# Sheet1.net
KiCad netlist of a schematic drawn in Altium Designer
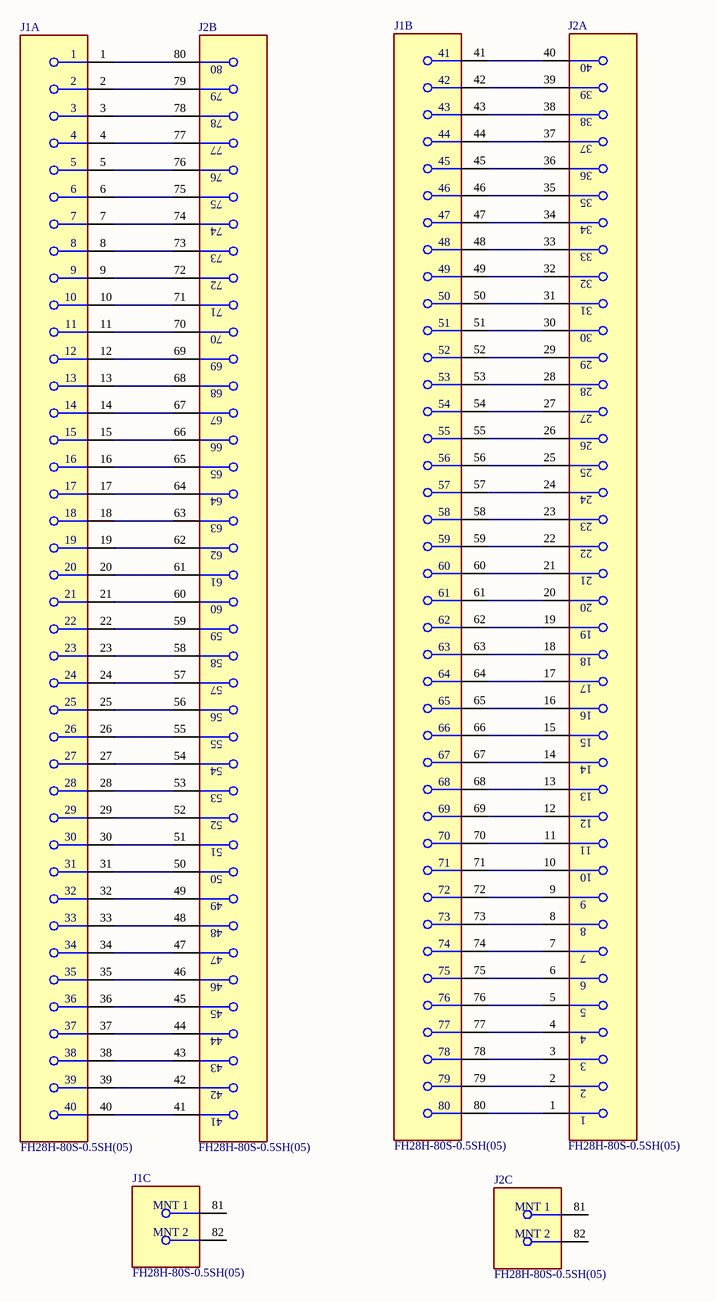
[diagram p0: Sheet1.SchDoc]

(export (version "E")
  (design (tool "Eeschema 10.0.6"))
  (components
    (comp (ref "J1")
      (value "FH28H-80S-0.5SH(05)")
      (footprint "FP-FH28H-80S-0_5SH_05-MFG")
      (description "CONN FFC BOTTOM 80POS 0.50MM R/A")
      (libsource (lib "") (part "08075b3669470a400ec152efcfe4938_1"))
    )
    (comp (ref "J2")
      (value "FH28H-80S-0.5SH(05)")
      (footprint "FP-FH28H-80S-0_5SH_05-MFG")
      (description "CONN FFC BOTTOM 80POS 0.50MM R/A")
      (libsource (lib "") (part "08075b3669470a400ec152efcfe4938_1"))
    )
  )
  (nets
    (net (code "1") (name "Net-(J1-Pad1)") (class "Default")
      (node (ref "J1") (pin "1") (pinfunction "1_1") (pintype "passive"))
      (node (ref "J2") (pin "80") (pinfunction "80_80") (pintype "passive"))
    )
    (net (code "2") (name "Net-(J1-Pad2)") (class "Default")
      (node (ref "J1") (pin "2") (pinfunction "2_2") (pintype "passive"))
      (node (ref "J2") (pin "79") (pinfunction "79_79") (pintype "passive"))
    )
    (net (code "3") (name "Net-(J1-Pad3)") (class "Default")
      (node (ref "J1") (pin "3") (pinfunction "3_3") (pintype "passive"))
      (node (ref "J2") (pin "78") (pinfunction "78_78") (pintype "passive"))
    )
    (net (code "4") (name "Net-(J1-Pad4)") (class "Default")
      (node (ref "J1") (pin "4") (pinfunction "4_4") (pintype "passive"))
      (node (ref "J2") (pin "77") (pinfunction "77_77") (pintype "passive"))
    )
    (net (code "5") (name "Net-(J1-Pad5)") (class "Default")
      (node (ref "J1") (pin "5") (pinfunction "5_5") (pintype "passive"))
      (node (ref "J2") (pin "76") (pinfunction "76_76") (pintype "passive"))
    )
    (net (code "6") (name "Net-(J1-Pad6)") (class "Default")
      (node (ref "J1") (pin "6") (pinfunction "6_6") (pintype "passive"))
      (node (ref "J2") (pin "75") (pinfunction "75_75") (pintype "passive"))
    )
    (net (code "7") (name "Net-(J1-Pad7)") (class "Default")
      (node (ref "J1") (pin "7") (pinfunction "7_7") (pintype "passive"))
      (node (ref "J2") (pin "74") (pinfunction "74_74") (pintype "passive"))
    )
    (net (code "8") (name "Net-(J1-Pad8)") (class "Default")
      (node (ref "J1") (pin "8") (pinfunction "8_8") (pintype "passive"))
      (node (ref "J2") (pin "73") (pinfunction "73_73") (pintype "passive"))
    )
    (net (code "9") (name "Net-(J1-Pad9)") (class "Default")
      (node (ref "J1") (pin "9") (pinfunction "9_9") (pintype "passive"))
      (node (ref "J2") (pin "72") (pinfunction "72_72") (pintype "passive"))
    )
    (net (code "10") (name "Net-(J1-Pad10)") (class "Default")
      (node (ref "J1") (pin "10") (pinfunction "10_10") (pintype "passive"))
      (node (ref "J2") (pin "71") (pinfunction "71_71") (pintype "passive"))
    )
    (net (code "11") (name "Net-(J1-Pad11)") (class "Default")
      (node (ref "J1") (pin "11") (pinfunction "11_11") (pintype "passive"))
      (node (ref "J2") (pin "70") (pinfunction "70_70") (pintype "passive"))
    )
    (net (code "12") (name "Net-(J1-Pad12)") (class "Default")
      (node (ref "J1") (pin "12") (pinfunction "12_12") (pintype "passive"))
      (node (ref "J2") (pin "69") (pinfunction "69_69") (pintype "passive"))
    )
    (net (code "13") (name "Net-(J1-Pad13)") (class "Default")
      (node (ref "J1") (pin "13") (pinfunction "13_13") (pintype "passive"))
      (node (ref "J2") (pin "68") (pinfunction "68_68") (pintype "passive"))
    )
    (net (code "14") (name "Net-(J1-Pad14)") (class "Default")
      (node (ref "J1") (pin "14") (pinfunction "14_14") (pintype "passive"))
      (node (ref "J2") (pin "67") (pinfunction "67_67") (pintype "passive"))
    )
    (net (code "15") (name "Net-(J1-Pad15)") (class "Default")
      (node (ref "J1") (pin "15") (pinfunction "15_15") (pintype "passive"))
      (node (ref "J2") (pin "66") (pinfunction "66_66") (pintype "passive"))
    )
    (net (code "16") (name "Net-(J1-Pad16)") (class "Default")
      (node (ref "J1") (pin "16") (pinfunction "16_16") (pintype "passive"))
      (node (ref "J2") (pin "65") (pinfunction "65_65") (pintype "passive"))
    )
    (net (code "17") (name "Net-(J1-Pad17)") (class "Default")
      (node (ref "J1") (pin "17") (pinfunction "17_17") (pintype "passive"))
      (node (ref "J2") (pin "64") (pinfunction "64_64") (pintype "passive"))
    )
    (net (code "18") (name "Net-(J1-Pad18)") (class "Default")
      (node (ref "J1") (pin "18") (pinfunction "18_18") (pintype "passive"))
      (node (ref "J2") (pin "63") (pinfunction "63_63") (pintype "passive"))
    )
    (net (code "19") (name "Net-(J1-Pad19)") (class "Default")
      (node (ref "J1") (pin "19") (pinfunction "19_19") (pintype "passive"))
      (node (ref "J2") (pin "62") (pinfunction "62_62") (pintype "passive"))
    )
    (net (code "20") (name "Net-(J1-Pad20)") (class "Default")
      (node (ref "J1") (pin "20") (pinfunction "20_20") (pintype "passive"))
      (node (ref "J2") (pin "61") (pinfunction "61_61") (pintype "passive"))
    )
    (net (code "21") (name "Net-(J1-Pad21)") (class "Default")
      (node (ref "J1") (pin "21") (pinfunction "21_21") (pintype "passive"))
      (node (ref "J2") (pin "60") (pinfunction "60_60") (pintype "passive"))
    )
    (net (code "22") (name "Net-(J1-Pad22)") (class "Default")
      (node (ref "J1") (pin "22") (pinfunction "22_22") (pintype "passive"))
      (node (ref "J2") (pin "59") (pinfunction "59_59") (pintype "passive"))
    )
    (net (code "23") (name "Net-(J1-Pad23)") (class "Default")
      (node (ref "J1") (pin "23") (pinfunction "23_23") (pintype "passive"))
      (node (ref "J2") (pin "58") (pinfunction "58_58") (pintype "passive"))
    )
    (net (code "24") (name "Net-(J1-Pad24)") (class "Default")
      (node (ref "J1") (pin "24") (pinfunction "24_24") (pintype "passive"))
      (node (ref "J2") (pin "57") (pinfunction "57_57") (pintype "passive"))
    )
    (net (code "25") (name "Net-(J1-Pad25)") (class "Default")
      (node (ref "J1") (pin "25") (pinfunction "25_25") (pintype "passive"))
      (node (ref "J2") (pin "56") (pinfunction "56_56") (pintype "passive"))
    )
    (net (code "26") (name "Net-(J1-Pad26)") (class "Default")
      (node (ref "J1") (pin "26") (pinfunction "26_26") (pintype "passive"))
      (node (ref "J2") (pin "55") (pinfunction "55_55") (pintype "passive"))
    )
    (net (code "27") (name "Net-(J1-Pad27)") (class "Default")
      (node (ref "J1") (pin "27") (pinfunction "27_27") (pintype "passive"))
      (node (ref "J2") (pin "54") (pinfunction "54_54") (pintype "passive"))
    )
    (net (code "28") (name "Net-(J1-Pad28)") (class "Default")
      (node (ref "J1") (pin "28") (pinfunction "28_28") (pintype "passive"))
      (node (ref "J2") (pin "53") (pinfunction "53_53") (pintype "passive"))
    )
    (net (code "29") (name "Net-(J1-Pad29)") (class "Default")
      (node (ref "J1") (pin "29") (pinfunction "29_29") (pintype "passive"))
      (node (ref "J2") (pin "52") (pinfunction "52_52") (pintype "passive"))
    )
    (net (code "30") (name "Net-(J1-Pad30)") (class "Default")
      (node (ref "J1") (pin "30") (pinfunction "30_30") (pintype "passive"))
      (node (ref "J2") (pin "51") (pinfunction "51_51") (pintype "passive"))
    )
    (net (code "31") (name "Net-(J1-Pad31)") (class "Default")
      (node (ref "J1") (pin "31") (pinfunction "31_31") (pintype "passive"))
      (node (ref "J2") (pin "50") (pinfunction "50_50") (pintype "passive"))
    )
    (net (code "32") (name "Net-(J1-Pad32)") (class "Default")
      (node (ref "J1") (pin "32") (pinfunction "32_32") (pintype "passive"))
      (node (ref "J2") (pin "49") (pinfunction "49_49") (pintype "passive"))
    )
    (net (code "33") (name "Net-(J1-Pad33)") (class "Default")
      (node (ref "J1") (pin "33") (pinfunction "33_33") (pintype "passive"))
      (node (ref "J2") (pin "48") (pinfunction "48_48") (pintype "passive"))
    )
    (net (code "34") (name "Net-(J1-Pad34)") (class "Default")
      (node (ref "J1") (pin "34") (pinfunction "34_34") (pintype "passive"))
      (node (ref "J2") (pin "47") (pinfunction "47_47") (pintype "passive"))
    )
    (net (code "35") (name "Net-(J1-Pad35)") (class "Default")
      (node (ref "J1") (pin "35") (pinfunction "35_35") (pintype "passive"))
      (node (ref "J2") (pin "46") (pinfunction "46_46") (pintype "passive"))
    )
    (net (code "36") (name "Net-(J1-Pad36)") (class "Default")
      (node (ref "J1") (pin "36") (pinfunction "36_36") (pintype "passive"))
      (node (ref "J2") (pin "45") (pinfunction "45_45") (pintype "passive"))
    )
    (net (code "37") (name "Net-(J1-Pad37)") (class "Default")
      (node (ref "J1") (pin "37") (pinfunction "37_37") (pintype "passive"))
      (node (ref "J2") (pin "44") (pinfunction "44_44") (pintype "passive"))
    )
    (net (code "38") (name "Net-(J1-Pad38)") (class "Default")
      (node (ref "J1") (pin "38") (pinfunction "38_38") (pintype "passive"))
      (node (ref "J2") (pin "43") (pinfunction "43_43") (pintype "passive"))
    )
    (net (code "39") (name "Net-(J1-Pad39)") (class "Default")
      (node (ref "J1") (pin "39") (pinfunction "39_39") (pintype "passive"))
      (node (ref "J2") (pin "42") (pinfunction "42_42") (pintype "passive"))
    )
    (net (code "40") (name "Net-(J1-Pad40)") (class "Default")
      (node (ref "J1") (pin "40") (pinfunction "40_40") (pintype "passive"))
      (node (ref "J2") (pin "41") (pinfunction "41_41") (pintype "passive"))
    )
    (net (code "41") (name "Net-(J1-Pad41)") (class "Default")
      (node (ref "J1") (pin "41") (pinfunction "41_41") (pintype "passive"))
      (node (ref "J2") (pin "40") (pinfunction "40_40") (pintype "passive"))
    )
    (net (code "42") (name "Net-(J1-Pad42)") (class "Default")
      (node (ref "J1") (pin "42") (pinfunction "42_42") (pintype "passive"))
      (node (ref "J2") (pin "39") (pinfunction "39_39") (pintype "passive"))
    )
    (net (code "43") (name "Net-(J1-Pad43)") (class "Default")
      (node (ref "J1") (pin "43") (pinfunction "43_43") (pintype "passive"))
      (node (ref "J2") (pin "38") (pinfunction "38_38") (pintype "passive"))
    )
    (net (code "44") (name "Net-(J1-Pad44)") (class "Default")
      (node (ref "J1") (pin "44") (pinfunction "44_44") (pintype "passive"))
      (node (ref "J2") (pin "37") (pinfunction "37_37") (pintype "passive"))
    )
    (net (code "45") (name "Net-(J1-Pad45)") (class "Default")
      (node (ref "J1") (pin "45") (pinfunction "45_45") (pintype "passive"))
      (node (ref "J2") (pin "36") (pinfunction "36_36") (pintype "passive"))
    )
    (net (code "46") (name "Net-(J1-Pad46)") (class "Default")
      (node (ref "J1") (pin "46") (pinfunction "46_46") (pintype "passive"))
      (node (ref "J2") (pin "35") (pinfunction "35_35") (pintype "passive"))
    )
    (net (code "47") (name "Net-(J1-Pad47)") (class "Default")
      (node (ref "J1") (pin "47") (pinfunction "47_47") (pintype "passive"))
      (node (ref "J2") (pin "34") (pinfunction "34_34") (pintype "passive"))
    )
    (net (code "48") (name "Net-(J1-Pad48)") (class "Default")
      (node (ref "J1") (pin "48") (pinfunction "48_48") (pintype "passive"))
      (node (ref "J2") (pin "33") (pinfunction "33_33") (pintype "passive"))
    )
    (net (code "49") (name "Net-(J1-Pad49)") (class "Default")
      (node (ref "J1") (pin "49") (pinfunction "49_49") (pintype "passive"))
      (node (ref "J2") (pin "32") (pinfunction "32_32") (pintype "passive"))
    )
    (net (code "50") (name "Net-(J1-Pad50)") (class "Default")
      (node (ref "J1") (pin "50") (pinfunction "50_50") (pintype "passive"))
      (node (ref "J2") (pin "31") (pinfunction "31_31") (pintype "passive"))
    )
    (net (code "51") (name "Net-(J1-Pad51)") (class "Default")
      (node (ref "J1") (pin "51") (pinfunction "51_51") (pintype "passive"))
      (node (ref "J2") (pin "30") (pinfunction "30_30") (pintype "passive"))
    )
    (net (code "52") (name "Net-(J1-Pad52)") (class "Default")
      (node (ref "J1") (pin "52") (pinfunction "52_52") (pintype "passive"))
      (node (ref "J2") (pin "29") (pinfunction "29_29") (pintype "passive"))
    )
    (net (code "53") (name "Net-(J1-Pad53)") (class "Default")
      (node (ref "J1") (pin "53") (pinfunction "53_53") (pintype "passive"))
      (node (ref "J2") (pin "28") (pinfunction "28_28") (pintype "passive"))
    )
    (net (code "54") (name "Net-(J1-Pad54)") (class "Default")
      (node (ref "J1") (pin "54") (pinfunction "54_54") (pintype "passive"))
      (node (ref "J2") (pin "27") (pinfunction "27_27") (pintype "passive"))
    )
    (net (code "55") (name "Net-(J1-Pad55)") (class "Default")
      (node (ref "J1") (pin "55") (pinfunction "55_55") (pintype "passive"))
      (node (ref "J2") (pin "26") (pinfunction "26_26") (pintype "passive"))
    )
    (net (code "56") (name "Net-(J1-Pad56)") (class "Default")
      (node (ref "J1") (pin "56") (pinfunction "56_56") (pintype "passive"))
      (node (ref "J2") (pin "25") (pinfunction "25_25") (pintype "passive"))
    )
    (net (code "57") (name "Net-(J1-Pad57)") (class "Default")
      (node (ref "J1") (pin "57") (pinfunction "57_57") (pintype "passive"))
      (node (ref "J2") (pin "24") (pinfunction "24_24") (pintype "passive"))
    )
    (net (code "58") (name "Net-(J1-Pad58)") (class "Default")
      (node (ref "J1") (pin "58") (pinfunction "58_58") (pintype "passive"))
      (node (ref "J2") (pin "23") (pinfunction "23_23") (pintype "passive"))
    )
    (net (code "59") (name "Net-(J1-Pad59)") (class "Default")
      (node (ref "J1") (pin "59") (pinfunction "59_59") (pintype "passive"))
      (node (ref "J2") (pin "22") (pinfunction "22_22") (pintype "passive"))
    )
    (net (code "60") (name "Net-(J1-Pad60)") (class "Default")
      (node (ref "J1") (pin "60") (pinfunction "60_60") (pintype "passive"))
      (node (ref "J2") (pin "21") (pinfunction "21_21") (pintype "passive"))
    )
    (net (code "61") (name "Net-(J1-Pad61)") (class "Default")
      (node (ref "J1") (pin "61") (pinfunction "61_61") (pintype "passive"))
      (node (ref "J2") (pin "20") (pinfunction "20_20") (pintype "passive"))
    )
    (net (code "62") (name "Net-(J1-Pad62)") (class "Default")
      (node (ref "J1") (pin "62") (pinfunction "62_62") (pintype "passive"))
      (node (ref "J2") (pin "19") (pinfunction "19_19") (pintype "passive"))
    )
    (net (code "63") (name "Net-(J1-Pad63)") (class "Default")
      (node (ref "J1") (pin "63") (pinfunction "63_63") (pintype "passive"))
      (node (ref "J2") (pin "18") (pinfunction "18_18") (pintype "passive"))
    )
    (net (code "64") (name "Net-(J1-Pad64)") (class "Default")
      (node (ref "J1") (pin "64") (pinfunction "64_64") (pintype "passive"))
      (node (ref "J2") (pin "17") (pinfunction "17_17") (pintype "passive"))
    )
    (net (code "65") (name "Net-(J1-Pad65)") (class "Default")
      (node (ref "J1") (pin "65") (pinfunction "65_65") (pintype "passive"))
      (node (ref "J2") (pin "16") (pinfunction "16_16") (pintype "passive"))
    )
    (net (code "66") (name "Net-(J1-Pad66)") (class "Default")
      (node (ref "J1") (pin "66") (pinfunction "66_66") (pintype "passive"))
      (node (ref "J2") (pin "15") (pinfunction "15_15") (pintype "passive"))
    )
    (net (code "67") (name "Net-(J1-Pad67)") (class "Default")
      (node (ref "J1") (pin "67") (pinfunction "67_67") (pintype "passive"))
      (node (ref "J2") (pin "14") (pinfunction "14_14") (pintype "passive"))
    )
    (net (code "68") (name "Net-(J1-Pad68)") (class "Default")
      (node (ref "J1") (pin "68") (pinfunction "68_68") (pintype "passive"))
      (node (ref "J2") (pin "13") (pinfunction "13_13") (pintype "passive"))
    )
    (net (code "69") (name "Net-(J1-Pad69)") (class "Default")
      (node (ref "J1") (pin "69") (pinfunction "69_69") (pintype "passive"))
      (node (ref "J2") (pin "12") (pinfunction "12_12") (pintype "passive"))
    )
    (net (code "70") (name "Net-(J1-Pad70)") (class "Default")
      (node (ref "J1") (pin "70") (pinfunction "70_70") (pintype "passive"))
      (node (ref "J2") (pin "11") (pinfunction "11_11") (pintype "passive"))
    )
    (net (code "71") (name "Net-(J1-Pad71)") (class "Default")
      (node (ref "J1") (pin "71") (pinfunction "71_71") (pintype "passive"))
      (node (ref "J2") (pin "10") (pinfunction "10_10") (pintype "passive"))
    )
    (net (code "72") (name "Net-(J1-Pad72)") (class "Default")
      (node (ref "J1") (pin "72") (pinfunction "72_72") (pintype "passive"))
      (node (ref "J2") (pin "9") (pinfunction "9_9") (pintype "passive"))
    )
    (net (code "73") (name "Net-(J1-Pad73)") (class "Default")
      (node (ref "J1") (pin "73") (pinfunction "73_73") (pintype "passive"))
      (node (ref "J2") (pin "8") (pinfunction "8_8") (pintype "passive"))
    )
    (net (code "74") (name "Net-(J1-Pad74)") (class "Default")
      (node (ref "J1") (pin "74") (pinfunction "74_74") (pintype "passive"))
      (node (ref "J2") (pin "7") (pinfunction "7_7") (pintype "passive"))
    )
    (net (code "75") (name "Net-(J1-Pad75)") (class "Default")
      (node (ref "J1") (pin "75") (pinfunction "75_75") (pintype "passive"))
      (node (ref "J2") (pin "6") (pinfunction "6_6") (pintype "passive"))
    )
    (net (code "76") (name "Net-(J1-Pad76)") (class "Default")
      (node (ref "J1") (pin "76") (pinfunction "76_76") (pintype "passive"))
      (node (ref "J2") (pin "5") (pinfunction "5_5") (pintype "passive"))
    )
    (net (code "77") (name "Net-(J1-Pad77)") (class "Default")
      (node (ref "J1") (pin "77") (pinfunction "77_77") (pintype "passive"))
      (node (ref "J2") (pin "4") (pinfunction "4_4") (pintype "passive"))
    )
    (net (code "78") (name "Net-(J1-Pad78)") (class "Default")
      (node (ref "J1") (pin "78") (pinfunction "78_78") (pintype "passive"))
      (node (ref "J2") (pin "3") (pinfunction "3_3") (pintype "passive"))
    )
    (net (code "79") (name "Net-(J1-Pad79)") (class "Default")
      (node (ref "J1") (pin "79") (pinfunction "79_79") (pintype "passive"))
      (node (ref "J2") (pin "2") (pinfunction "2_2") (pintype "passive"))
    )
    (net (code "80") (name "Net-(J1-Pad80)") (class "Default")
      (node (ref "J1") (pin "80") (pinfunction "80_80") (pintype "passive"))
      (node (ref "J2") (pin "1") (pinfunction "1_1") (pintype "passive"))
    )
    (net (code "81") (name "unconnected-(J1C-MNT_1-Pad81)") (class "Default")
      (node (ref "J1") (pin "81") (pinfunction "MNT_1_81") (pintype "passive"))
    )
    (net (code "82") (name "unconnected-(J1C-MNT_2-Pad82)") (class "Default")
      (node (ref "J1") (pin "82") (pinfunction "MNT_2_82") (pintype "passive"))
    )
    (net (code "83") (name "unconnected-(J2C-MNT_1-Pad81)") (class "Default")
      (node (ref "J2") (pin "81") (pinfunction "MNT_1_81") (pintype "passive"))
    )
    (net (code "84") (name "unconnected-(J2C-MNT_2-Pad82)") (class "Default")
      (node (ref "J2") (pin "82") (pinfunction "MNT_2_82") (pintype "passive"))
    )
  )
)
